# Communication.net
KiCad netlist of a schematic drawn in Altium Designer
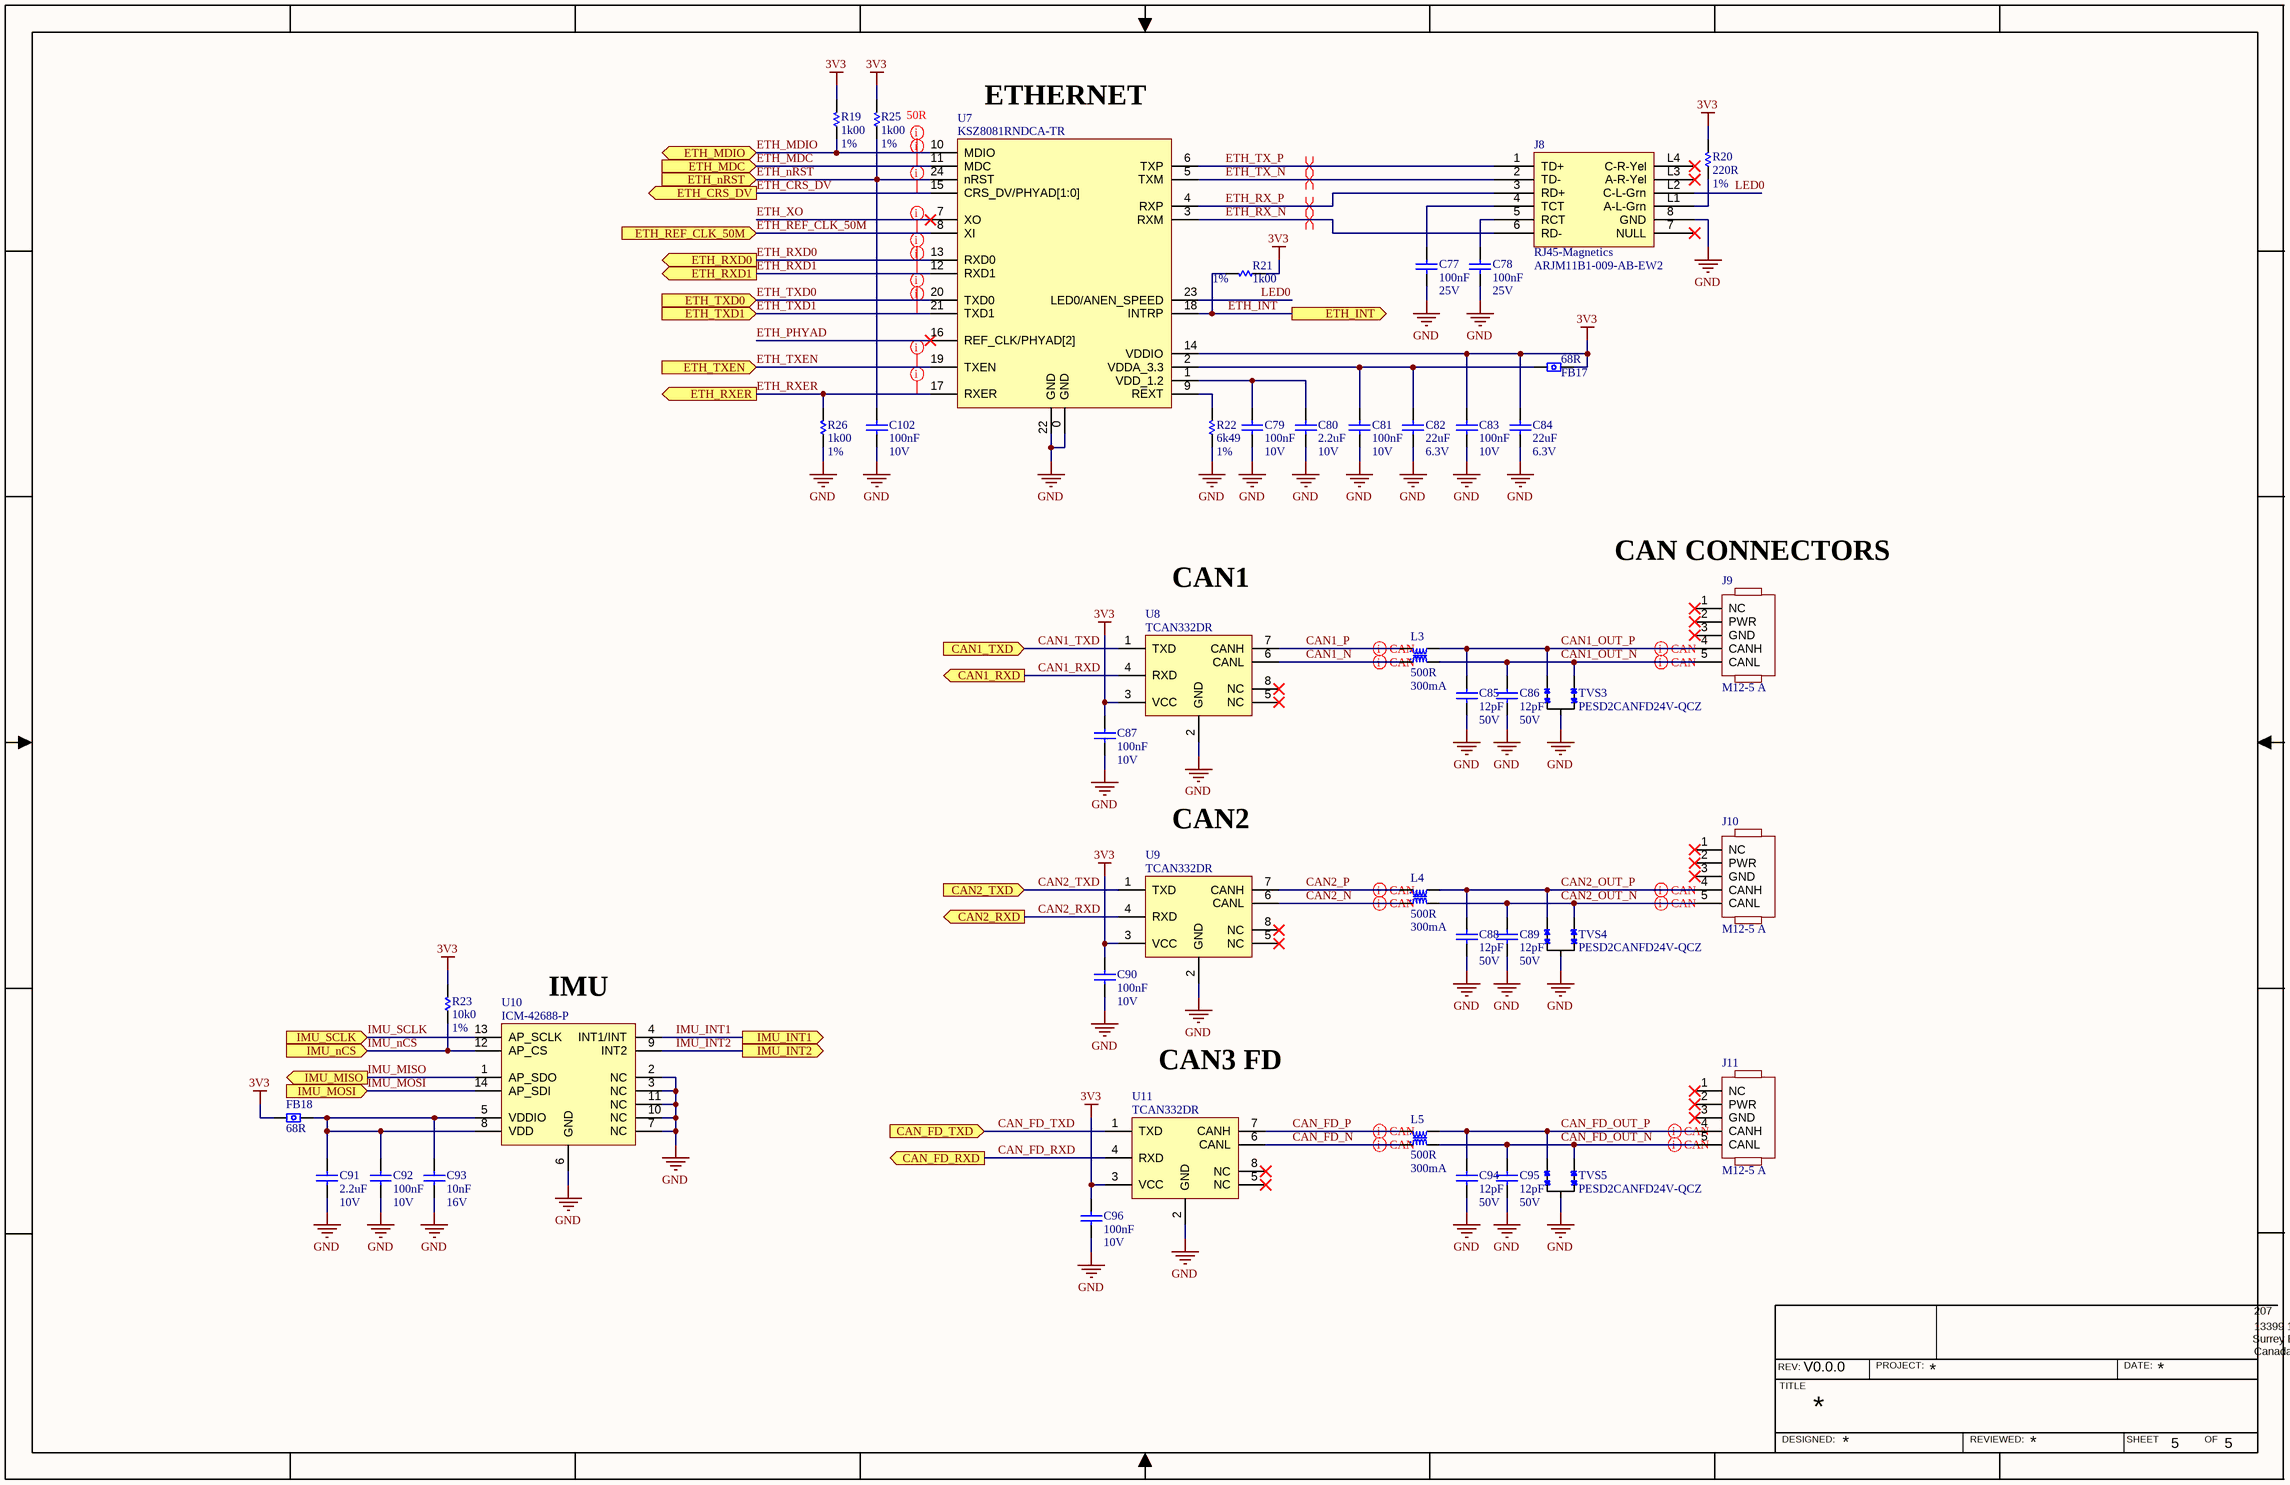
[diagram p0: Communication.SchDoc]

(export (version "E")
  (design (tool "Eeschema 10.0.6"))
  (components
    (comp (ref "C77")
      (value "100nF")
      (footprint "C0402")
      (description "Cap Ceramic 0.1uF 25V X5R 10% Pad SMD 0402 85°C T/R / Multi Layer Ceramic Capacitor (MLCC)")
      (fields
        (field (name "MANUFACTURER") "Samsung")
        (field (name "MANUFACTURER PART NUMBER") "CL05A104KA5NNNC")
        (field (name "VOLTAGE RATING") "25V")
      )
      (libsource (lib "MCU") (part "CAP CER 100nF 25V X5R 0402"))
    )
    (comp (ref "C78")
      (value "100nF")
      (footprint "C0402")
      (description "Cap Ceramic 0.1uF 25V X5R 10% Pad SMD 0402 85°C T/R / Multi Layer Ceramic Capacitor (MLCC)")
      (fields
        (field (name "MANUFACTURER") "Samsung")
        (field (name "MANUFACTURER PART NUMBER") "CL05A104KA5NNNC")
        (field (name "VOLTAGE RATING") "25V")
      )
      (libsource (lib "MCU") (part "CAP CER 100nF 25V X5R 0402"))
    )
    (comp (ref "C79")
      (value "100nF")
      (footprint "C0201")
      (description "CAP CER 0.1UF 10V X5R 0201")
      (fields (field (name "TOLERANCE") "20%") (field (name "VOLTAGE RATING") "10V"))
      (libsource (lib "MCU") (part "CAP CER 100nF 10V X5R 0201"))
    )
    (comp (ref "C80")
      (value "2.2uF")
      (footprint "C0402")
      (fields
        (field (name "MANUFACTURER") "Taiyo Yuden")
        (field (name "MANUFACTURER PART NUMBER") "LMK105BJ225MV-F")
        (field (name "TOLERANCE") "20%")
        (field (name "VOLTAGE RATING") "10V")
      )
      (libsource (lib "MCU") (part "CAP CER 2.2uF 10V X5R 0402"))
    )
    (comp (ref "C81")
      (value "100nF")
      (footprint "C0201")
      (description "CAP CER 0.1UF 10V X5R 0201")
      (fields (field (name "TOLERANCE") "20%") (field (name "VOLTAGE RATING") "10V"))
      (libsource (lib "MCU") (part "CAP CER 100nF 10V X5R 0201"))
    )
    (comp (ref "C82")
      (value "22uF")
      (footprint "C0805")
      (description "CAP CER 22UF 6.3V X5R 0805 / Cap Ceramic 22uF 6.3V X5R 20% Pad SMD 0805 85°C T/R")
      (fields
        (field (name "MANUFACTURER") "Samsung")
        (field (name "MANUFACTURER PART NUMBER") "CL21A226MQQNNNE")
        (field (name "VOLTAGE RATING (DC)") "6.3V")
      )
      (libsource (lib "MCU") (part "CAP CER 22uF 6.3V X5R 0805"))
    )
    (comp (ref "C83")
      (value "100nF")
      (footprint "C0201")
      (description "CAP CER 0.1UF 10V X5R 0201")
      (fields (field (name "TOLERANCE") "20%") (field (name "VOLTAGE RATING") "10V"))
      (libsource (lib "MCU") (part "CAP CER 100nF 10V X5R 0201"))
    )
    (comp (ref "C84")
      (value "22uF")
      (footprint "C0805")
      (description "CAP CER 22UF 6.3V X5R 0805 / Cap Ceramic 22uF 6.3V X5R 20% Pad SMD 0805 85°C T/R")
      (fields
        (field (name "MANUFACTURER") "Samsung")
        (field (name "MANUFACTURER PART NUMBER") "CL21A226MQQNNNE")
        (field (name "VOLTAGE RATING (DC)") "6.3V")
      )
      (libsource (lib "MCU") (part "CAP CER 22uF 6.3V X5R 0805"))
    )
    (comp (ref "C85")
      (value "12pF")
      (footprint "C0402")
      (description "Ceramic capacitor SMD-0402 12pF /50V C0G# J +-5%, Samsung, RoHS")
      (fields
        (field (name "MANUFACTURER") "Samsung")
        (field (name "MANUFACTURER PART NUMBER") "CL05C120JB5NNNC")
        (field (name "VOLTAGE") "50V")
      )
      (libsource (lib "MCU") (part "CAP CER 12pF 50V C0G 0402"))
    )
    (comp (ref "C86")
      (value "12pF")
      (footprint "C0402")
      (description "Ceramic capacitor SMD-0402 12pF /50V C0G# J +-5%, Samsung, RoHS")
      (fields
        (field (name "MANUFACTURER") "Samsung")
        (field (name "MANUFACTURER PART NUMBER") "CL05C120JB5NNNC")
        (field (name "VOLTAGE") "50V")
      )
      (libsource (lib "MCU") (part "CAP CER 12pF 50V C0G 0402"))
    )
    (comp (ref "C87")
      (value "100nF")
      (footprint "C0201")
      (description "CAP CER 0.1UF 10V X5R 0201")
      (fields (field (name "TOLERANCE") "20%") (field (name "VOLTAGE RATING") "10V"))
      (libsource (lib "MCU") (part "CAP CER 100nF 10V X5R 0201"))
    )
    (comp (ref "C88")
      (value "12pF")
      (footprint "C0402")
      (description "Ceramic capacitor SMD-0402 12pF /50V C0G# J +-5%, Samsung, RoHS")
      (fields
        (field (name "MANUFACTURER") "Samsung")
        (field (name "MANUFACTURER PART NUMBER") "CL05C120JB5NNNC")
        (field (name "VOLTAGE") "50V")
      )
      (libsource (lib "MCU") (part "CAP CER 12pF 50V C0G 0402"))
    )
    (comp (ref "C89")
      (value "12pF")
      (footprint "C0402")
      (description "Ceramic capacitor SMD-0402 12pF /50V C0G# J +-5%, Samsung, RoHS")
      (fields
        (field (name "MANUFACTURER") "Samsung")
        (field (name "MANUFACTURER PART NUMBER") "CL05C120JB5NNNC")
        (field (name "VOLTAGE") "50V")
      )
      (libsource (lib "MCU") (part "CAP CER 12pF 50V C0G 0402"))
    )
    (comp (ref "C90")
      (value "100nF")
      (footprint "C0201")
      (description "CAP CER 0.1UF 10V X5R 0201")
      (fields (field (name "TOLERANCE") "20%") (field (name "VOLTAGE RATING") "10V"))
      (libsource (lib "MCU") (part "CAP CER 100nF 10V X5R 0201"))
    )
    (comp (ref "C91")
      (value "2.2uF")
      (footprint "C0402")
      (fields
        (field (name "MANUFACTURER") "Taiyo Yuden")
        (field (name "MANUFACTURER PART NUMBER") "LMK105BJ225MV-F")
        (field (name "TOLERANCE") "20%")
        (field (name "VOLTAGE RATING") "10V")
      )
      (libsource (lib "MCU") (part "CAP CER 2.2uF 10V X5R 0402"))
    )
    (comp (ref "C92")
      (value "100nF")
      (footprint "C0201")
      (description "CAP CER 0.1UF 10V X5R 0201")
      (fields (field (name "TOLERANCE") "20%") (field (name "VOLTAGE RATING") "10V"))
      (libsource (lib "MCU") (part "CAP CER 100nF 10V X5R 0201"))
    )
    (comp (ref "C93")
      (value "10nF")
      (footprint "c0402")
      (description "0402 10 nF 16 V -20 / +80 % Tolerance Y5V SMT Multilayer Ceramic Capacitor")
      (fields
        (field (name "MANUFACTURER") "Yageo")
        (field (name "MANUFACTURER PART NUMBER") "CC0402ZRY5V7BB103")
        (field (name "VOLTAGE RATING") "16V")
      )
      (libsource (lib "MCU") (part "CAP CER 10nF 16V Y5V 0402"))
    )
    (comp (ref "C94")
      (value "12pF")
      (footprint "C0402")
      (description "Ceramic capacitor SMD-0402 12pF /50V C0G# J +-5%, Samsung, RoHS")
      (fields
        (field (name "MANUFACTURER") "Samsung")
        (field (name "MANUFACTURER PART NUMBER") "CL05C120JB5NNNC")
        (field (name "VOLTAGE") "50V")
      )
      (libsource (lib "MCU") (part "CAP CER 12pF 50V C0G 0402"))
    )
    (comp (ref "C95")
      (value "12pF")
      (footprint "C0402")
      (description "Ceramic capacitor SMD-0402 12pF /50V C0G# J +-5%, Samsung, RoHS")
      (fields
        (field (name "MANUFACTURER") "Samsung")
        (field (name "MANUFACTURER PART NUMBER") "CL05C120JB5NNNC")
        (field (name "VOLTAGE") "50V")
      )
      (libsource (lib "MCU") (part "CAP CER 12pF 50V C0G 0402"))
    )
    (comp (ref "C96")
      (value "100nF")
      (footprint "C0201")
      (description "CAP CER 0.1UF 10V X5R 0201")
      (fields (field (name "TOLERANCE") "20%") (field (name "VOLTAGE RATING") "10V"))
      (libsource (lib "MCU") (part "CAP CER 100nF 10V X5R 0201"))
    )
    (comp (ref "C102")
      (value "100nF")
      (footprint "C0201")
      (description "CAP CER 0.1UF 10V X5R 0201")
      (fields (field (name "TOLERANCE") "20%") (field (name "VOLTAGE RATING") "10V"))
      (libsource (lib "MCU") (part "CAP CER 100nF 10V X5R 0201"))
    )
    (comp (ref "FB17")
      (value "68R")
      (footprint "FB0402")
      (description "Ferrite Beads Multi-Layer 68Ohm 25% 100MHz 400mA 310mOhm DCR 0402 T/R")
      (fields
        (field (name "MANUFACTURER") "Taiyo Yuden")
        (field (name "MANUFACTURER PART NUMBER") "BK1005LL680-T")
      )
      (libsource (lib "MCU") (part "FB 68R 400mA 310mR 0402"))
    )
    (comp (ref "FB18")
      (value "68R")
      (footprint "FB0402")
      (description "Ferrite Beads Multi-Layer 68Ohm 25% 100MHz 400mA 310mOhm DCR 0402 T/R")
      (fields
        (field (name "MANUFACTURER") "Taiyo Yuden")
        (field (name "MANUFACTURER PART NUMBER") "BK1005LL680-T")
      )
      (libsource (lib "MCU") (part "FB 68R 400mA 310mR 0402"))
    )
    (comp (ref "J8")
      (value "RJ45-Magnetics")
      (footprint "RJ45_ARJM11B1_LED")
      (description "RJ45 Integrated T-Base 100 Magnetics")
      (fields (field (name "SUPPLIER PART NUMBER 1") "ARJM11B1-009-AB-EW2"))
      (libsource (lib "MCU") (part "ARJM11B1-009-AB-EW2"))
    )
    (comp (ref "J9")
      (value "M12-5 A")
      (footprint "M12-5A RA TH")
      (description "Connector, Circular, Plug, 5 Position, Right Angle, Panel Mount")
      (fields
        (field (name "MANUFACTURER") "TE Connectivity AMP")
        (field (name "MANUFACTURER PART NUMBER") "T4144015051-000")
      )
      (libsource (lib "MCU") (part "CON M12-5A T4144015051-000"))
    )
    (comp (ref "J10")
      (value "M12-5 A")
      (footprint "M12-5A RA TH")
      (description "Connector, Circular, Plug, 5 Position, Right Angle, Panel Mount")
      (fields
        (field (name "MANUFACTURER") "TE Connectivity AMP")
        (field (name "MANUFACTURER PART NUMBER") "T4144015051-000")
      )
      (libsource (lib "MCU") (part "CON M12-5A T4144015051-000"))
    )
    (comp (ref "J11")
      (value "M12-5 A")
      (footprint "M12-5A RA TH")
      (description "Connector, Circular, Plug, 5 Position, Right Angle, Panel Mount")
      (fields
        (field (name "MANUFACTURER") "TE Connectivity AMP")
        (field (name "MANUFACTURER PART NUMBER") "T4144015051-000")
      )
      (libsource (lib "MCU") (part "CON M12-5A T4144015051-000"))
    )
    (comp (ref "L3")
      (value "500R")
      (footprint "IND CHOKE 1.2x2")
      (description "Common Mode Chokes Dual 500Ohm 100MHz 300mA 500mOhm DCR SMD T/R")
      (fields
        (field (name "MANUFACTURER") "Bourns")
        (field (name "MANUFACTURER PART NUMBER") "SRF2012-501YA")
        (field (name "MAX CURRENT RATING") "300mA")
      )
      (libsource (lib "MCU") (part "IND CM 500R 300mA SRF2012-501YA"))
    )
    (comp (ref "L4")
      (value "500R")
      (footprint "IND CHOKE 1.2x2")
      (description "Common Mode Chokes Dual 500Ohm 100MHz 300mA 500mOhm DCR SMD T/R")
      (fields
        (field (name "MANUFACTURER") "Bourns")
        (field (name "MANUFACTURER PART NUMBER") "SRF2012-501YA")
        (field (name "MAX CURRENT RATING") "300mA")
      )
      (libsource (lib "MCU") (part "IND CM 500R 300mA SRF2012-501YA"))
    )
    (comp (ref "L5")
      (value "500R")
      (footprint "IND CHOKE 1.2x2")
      (description "Common Mode Chokes Dual 500Ohm 100MHz 300mA 500mOhm DCR SMD T/R")
      (fields
        (field (name "MANUFACTURER") "Bourns")
        (field (name "MANUFACTURER PART NUMBER") "SRF2012-501YA")
        (field (name "MAX CURRENT RATING") "300mA")
      )
      (libsource (lib "MCU") (part "IND CM 500R 300mA SRF2012-501YA"))
    )
    (comp (ref "R19")
      (value "1k00")
      (footprint "R0402")
      (description "1 kOhms ±1% 0.063W, 1/16W Chip Resistor 0402 (1005 Metric) Moisture Resistant Thick Film")
      (fields
        (field (name "MANUFACTURER") "Yageo")
        (field (name "MANUFACTURER PART NUMBER") "RC0402FR-071KL")
        (field (name "TOLERANCE") "1%")
      )
      (libsource (lib "MCU") (part "RES 1k00 63mW 0402"))
    )
    (comp (ref "R20")
      (value "220R")
      (footprint "R0402")
      (description "Res Thick Film 0402 220 Ohm 1% 0.063W ?100ppm/?C Molded SMD Paper T/R")
      (fields
        (field (name "MANUFACTURER") "Yageo")
        (field (name "MANUFACTURER PART NUMBER") "RC0402FR-07220RL")
        (field (name "TOLERANCE") "1%")
      )
      (libsource (lib "MCU") (part "RES 220R 1% 63mW 0402"))
    )
    (comp (ref "R21")
      (value "1k00")
      (footprint "R0402")
      (description "1 kOhms ±1% 0.063W, 1/16W Chip Resistor 0402 (1005 Metric) Moisture Resistant Thick Film")
      (fields
        (field (name "MANUFACTURER") "Yageo")
        (field (name "MANUFACTURER PART NUMBER") "RC0402FR-071KL")
        (field (name "TOLERANCE") "1%")
      )
      (libsource (lib "MCU") (part "RES 1k00 63mW 0402"))
    )
    (comp (ref "R22")
      (value "6k49")
      (footprint "r0402")
      (description "Res Thick Film 0402 6.49K Ohm 1% 1/10W ±100ppm/°C Molded SMD Punched Carrier T/R")
      (fields
        (field (name "MANUFACTURER") "Panasonic")
        (field (name "MANUFACTURER PART NUMBER") "ERJ-2RKF6491X")
        (field (name "TOLERANCE") "1%")
      )
      (libsource (lib "MCU") (part "RES 6k49 1% 63mW 0402"))
    )
    (comp (ref "R23")
      (value "10k0")
      (footprint "r0402")
      (description "Res General Purpose Thick Film 0402 10K Ohm 1% 1/16W ±100ppm/°C Molded SMD Paper T/R")
      (fields
        (field (name "MANUFACTURER") "Yageo")
        (field (name "MANUFACTURER PART NUMBER") "RC0402FR-0710KL")
        (field (name "TOLERANCE") "1%")
      )
      (libsource (lib "MCU") (part "RES 10k0 1% 63mW 0402"))
    )
    (comp (ref "R25")
      (value "1k00")
      (footprint "R0402")
      (description "1 kOhms ±1% 0.063W, 1/16W Chip Resistor 0402 (1005 Metric) Moisture Resistant Thick Film")
      (fields
        (field (name "MANUFACTURER") "Yageo")
        (field (name "MANUFACTURER PART NUMBER") "RC0402FR-071KL")
        (field (name "TOLERANCE") "1%")
      )
      (libsource (lib "MCU") (part "RES 1k00 63mW 0402"))
    )
    (comp (ref "R26")
      (value "1k00")
      (footprint "R0402")
      (description "1 kOhms ±1% 0.063W, 1/16W Chip Resistor 0402 (1005 Metric) Moisture Resistant Thick Film")
      (fields
        (field (name "MANUFACTURER") "Yageo")
        (field (name "MANUFACTURER PART NUMBER") "RC0402FR-071KL")
        (field (name "TOLERANCE") "1%")
      )
      (libsource (lib "MCU") (part "RES 1k00 63mW 0402"))
    )
    (comp (ref "TVS3")
      (value "PESD2CANFD24V-QCZ")
      (footprint "DFN1412D-3")
      (description "PESD2CANFD24V-QC - ESD protection for In-vehicle networks")
      (fields (field (name "MANUFACTURER") "Nexperia"))
      (libsource (lib "MCU") (part "DIODE TVS 24V 2chanPESD2CANFD24V-QCZ"))
    )
    (comp (ref "TVS4")
      (value "PESD2CANFD24V-QCZ")
      (footprint "DFN1412D-3")
      (description "PESD2CANFD24V-QC - ESD protection for In-vehicle networks")
      (fields (field (name "MANUFACTURER") "Nexperia"))
      (libsource (lib "MCU") (part "DIODE TVS 24V 2chanPESD2CANFD24V-QCZ"))
    )
    (comp (ref "TVS5")
      (value "PESD2CANFD24V-QCZ")
      (footprint "DFN1412D-3")
      (description "PESD2CANFD24V-QC - ESD protection for In-vehicle networks")
      (fields (field (name "MANUFACTURER") "Nexperia"))
      (libsource (lib "MCU") (part "DIODE TVS 24V 2chanPESD2CANFD24V-QCZ"))
    )
    (comp (ref "U7")
      (value "KSZ8081RNDCA-TR")
      (footprint "QFN50P400X400X90_HS-25N")
      (description "Ethernet PHY, 100Mbps, -40 to 85°C, VQFN-24, RoHS")
      (fields
        (field (name "MANUFACTURER") "Microchip")
        (field (name "MANUFACTURER PART NUMBER") "KSZ8081RNDCATR")
      )
      (libsource (lib "MCU") (part "IC ETH PHY 10-100M RMII KSZ8081RNDCATR"))
    )
    (comp (ref "U8")
      (value "TCAN332DR")
      (footprint "SO8 6.2x5mm TI D0008A")
      (description "IC TXRX CAN 3.3V 8SOIC")
      (fields (field (name "MANUFACTURER") "Texas Instruments"))
      (libsource (lib "MCU") (part "IC CAN TRX TCAN332DR"))
    )
    (comp (ref "U9")
      (value "TCAN332DR")
      (footprint "SO8 6.2x5mm TI D0008A")
      (description "IC TXRX CAN 3.3V 8SOIC")
      (fields (field (name "MANUFACTURER") "Texas Instruments"))
      (libsource (lib "MCU") (part "IC CAN TRX TCAN332DR"))
    )
    (comp (ref "U10")
      (value "ICM-42688-P")
      (footprint "PQFN50P300X250X97-14 ICM-42688-P")
      (description "Accelerometer and Gyroscope 6-Axis MEMS Motion Tracking Device Digital-OUT 14-Pin LGA T/R")
      (fields (field (name "MANUFACTURER") "TDK InvenSense"))
      (libsource (lib "MCU") (part "IC IMU 6DOF ICM-42688-P"))
    )
    (comp (ref "U11")
      (value "TCAN332DR")
      (footprint "SO8 6.2x5mm TI D0008A")
      (description "IC TXRX CAN 3.3V 8SOIC")
      (fields (field (name "MANUFACTURER") "Texas Instruments"))
      (libsource (lib "MCU") (part "IC CAN TRX TCAN332DR"))
    )
  )
  (nets
    (net (code "1") (name "/CAN1_N") (class "Default")
      (node (ref "L3") (pin "4") (pinfunction "4_4") (pintype "passive"))
      (node (ref "U8") (pin "6") (pinfunction "CANL_6") (pintype "passive"))
    )
    (net (code "2") (name "/CAN1_OUT_N") (class "Default")
      (node (ref "C86") (pin "2") (pinfunction "2_2") (pintype "passive"))
      (node (ref "J9") (pin "5") (pinfunction "CANL_5") (pintype "passive"))
      (node (ref "L3") (pin "3") (pinfunction "3_3") (pintype "passive"))
      (node (ref "TVS3") (pin "2") (pinfunction "2_2") (pintype "passive"))
    )
    (net (code "3") (name "/CAN1_OUT_P") (class "Default")
      (node (ref "C85") (pin "2") (pinfunction "2_2") (pintype "passive"))
      (node (ref "J9") (pin "4") (pinfunction "CANH_4") (pintype "passive"))
      (node (ref "L3") (pin "2") (pinfunction "2_2") (pintype "passive"))
      (node (ref "TVS3") (pin "1") (pinfunction "1_1") (pintype "passive"))
    )
    (net (code "4") (name "/CAN1_P") (class "Default")
      (node (ref "L3") (pin "1") (pinfunction "1_1") (pintype "passive"))
      (node (ref "U8") (pin "7") (pinfunction "CANH_7") (pintype "passive"))
    )
    (net (code "5") (name "/CAN1_RXD") (class "Default")
      (node (ref "U8") (pin "4") (pinfunction "RXD_4") (pintype "passive"))
    )
    (net (code "6") (name "/CAN1_TXD") (class "Default")
      (node (ref "U8") (pin "1") (pinfunction "TXD_1") (pintype "passive"))
    )
    (net (code "7") (name "/CAN2_N") (class "Default")
      (node (ref "L4") (pin "4") (pinfunction "4_4") (pintype "passive"))
      (node (ref "U9") (pin "6") (pinfunction "CANL_6") (pintype "passive"))
    )
    (net (code "8") (name "/CAN2_OUT_N") (class "Default")
      (node (ref "C89") (pin "2") (pinfunction "2_2") (pintype "passive"))
      (node (ref "J10") (pin "5") (pinfunction "CANL_5") (pintype "passive"))
      (node (ref "L4") (pin "3") (pinfunction "3_3") (pintype "passive"))
      (node (ref "TVS4") (pin "2") (pinfunction "2_2") (pintype "passive"))
    )
    (net (code "9") (name "/CAN2_OUT_P") (class "Default")
      (node (ref "C88") (pin "2") (pinfunction "2_2") (pintype "passive"))
      (node (ref "J10") (pin "4") (pinfunction "CANH_4") (pintype "passive"))
      (node (ref "L4") (pin "2") (pinfunction "2_2") (pintype "passive"))
      (node (ref "TVS4") (pin "1") (pinfunction "1_1") (pintype "passive"))
    )
    (net (code "10") (name "/CAN2_P") (class "Default")
      (node (ref "L4") (pin "1") (pinfunction "1_1") (pintype "passive"))
      (node (ref "U9") (pin "7") (pinfunction "CANH_7") (pintype "passive"))
    )
    (net (code "11") (name "/CAN2_RXD") (class "Default")
      (node (ref "U9") (pin "4") (pinfunction "RXD_4") (pintype "passive"))
    )
    (net (code "12") (name "/CAN2_TXD") (class "Default")
      (node (ref "U9") (pin "1") (pinfunction "TXD_1") (pintype "passive"))
    )
    (net (code "13") (name "/CAN_FD_N") (class "Default")
      (node (ref "L5") (pin "4") (pinfunction "4_4") (pintype "passive"))
      (node (ref "U11") (pin "6") (pinfunction "CANL_6") (pintype "passive"))
    )
    (net (code "14") (name "/CAN_FD_OUT_N") (class "Default")
      (node (ref "C95") (pin "2") (pinfunction "2_2") (pintype "passive"))
      (node (ref "J11") (pin "5") (pinfunction "CANL_5") (pintype "passive"))
      (node (ref "L5") (pin "3") (pinfunction "3_3") (pintype "passive"))
      (node (ref "TVS5") (pin "2") (pinfunction "2_2") (pintype "passive"))
    )
    (net (code "15") (name "/CAN_FD_OUT_P") (class "Default")
      (node (ref "C94") (pin "2") (pinfunction "2_2") (pintype "passive"))
      (node (ref "J11") (pin "4") (pinfunction "CANH_4") (pintype "passive"))
      (node (ref "L5") (pin "2") (pinfunction "2_2") (pintype "passive"))
      (node (ref "TVS5") (pin "1") (pinfunction "1_1") (pintype "passive"))
    )
    (net (code "16") (name "/CAN_FD_P") (class "Default")
      (node (ref "L5") (pin "1") (pinfunction "1_1") (pintype "passive"))
      (node (ref "U11") (pin "7") (pinfunction "CANH_7") (pintype "passive"))
    )
    (net (code "17") (name "/CAN_FD_RXD") (class "Default")
      (node (ref "U11") (pin "4") (pinfunction "RXD_4") (pintype "passive"))
    )
    (net (code "18") (name "/CAN_FD_TXD") (class "Default")
      (node (ref "U11") (pin "1") (pinfunction "TXD_1") (pintype "passive"))
    )
    (net (code "19") (name "/ETH_CRS_DV") (class "Default")
      (node (ref "U7") (pin "15") (pinfunction "CRS_DV/PHYAD[1:0]_15") (pintype "passive"))
    )
    (net (code "20") (name "/ETH_INT") (class "Default")
      (node (ref "R21") (pin "2") (pinfunction "2_2") (pintype "passive"))
      (node (ref "U7") (pin "18") (pinfunction "INTRP_18") (pintype "passive"))
    )
    (net (code "21") (name "/ETH_MDC") (class "Default")
      (node (ref "U7") (pin "11") (pinfunction "MDC_11") (pintype "passive"))
    )
    (net (code "22") (name "/ETH_MDIO") (class "Default")
      (node (ref "R19") (pin "1") (pinfunction "1_1") (pintype "passive"))
      (node (ref "U7") (pin "10") (pinfunction "MDIO_10") (pintype "passive"))
    )
    (net (code "23") (name "/ETH_PHYAD") (class "Default")
      (node (ref "U7") (pin "16") (pinfunction "REF_CLK/PHYAD[2]_16") (pintype "passive+no_connect"))
    )
    (net (code "24") (name "/ETH_REF_CLK_50M") (class "Default")
      (node (ref "U7") (pin "8") (pinfunction "XI_8") (pintype "passive"))
    )
    (net (code "25") (name "/ETH_RXD0") (class "Default")
      (node (ref "U7") (pin "13") (pinfunction "RXD0_13") (pintype "passive"))
    )
    (net (code "26") (name "/ETH_RXD1") (class "Default")
      (node (ref "U7") (pin "12") (pinfunction "RXD1_12") (pintype "passive"))
    )
    (net (code "27") (name "/ETH_RXER") (class "Default")
      (node (ref "R26") (pin "2") (pinfunction "2_2") (pintype "passive"))
      (node (ref "U7") (pin "17") (pinfunction "RXER_17") (pintype "passive"))
    )
    (net (code "28") (name "/ETH_RX_N") (class "Default")
      (node (ref "J8") (pin "6") (pinfunction "RD-_6") (pintype "passive"))
      (node (ref "U7") (pin "3") (pinfunction "RXM_3") (pintype "passive"))
    )
    (net (code "29") (name "/ETH_RX_P") (class "Default")
      (node (ref "J8") (pin "3") (pinfunction "RD+_3") (pintype "passive"))
      (node (ref "U7") (pin "4") (pinfunction "RXP_4") (pintype "passive"))
    )
    (net (code "30") (name "/ETH_TXD0") (class "Default")
      (node (ref "U7") (pin "20") (pinfunction "TXD0_20") (pintype "passive"))
    )
    (net (code "31") (name "/ETH_TXD1") (class "Default")
      (node (ref "U7") (pin "21") (pinfunction "TXD1_21") (pintype "passive"))
    )
    (net (code "32") (name "/ETH_TXEN") (class "Default")
      (node (ref "U7") (pin "19") (pinfunction "TXEN_19") (pintype "passive"))
    )
    (net (code "33") (name "/ETH_TX_N") (class "Default")
      (node (ref "J8") (pin "2") (pinfunction "TD-_2") (pintype "passive"))
      (node (ref "U7") (pin "5") (pinfunction "TXM_5") (pintype "passive"))
    )
    (net (code "34") (name "/ETH_TX_P") (class "Default")
      (node (ref "J8") (pin "1") (pinfunction "TD+_1") (pintype "passive"))
      (node (ref "U7") (pin "6") (pinfunction "TXP_6") (pintype "passive"))
    )
    (net (code "35") (name "/ETH_XO") (class "Default")
      (node (ref "U7") (pin "7") (pinfunction "XO_7") (pintype "passive+no_connect"))
    )
    (net (code "36") (name "/ETH_nRST") (class "Default")
      (node (ref "C102") (pin "2") (pinfunction "2_2") (pintype "passive"))
      (node (ref "R25") (pin "1") (pinfunction "1_1") (pintype "passive"))
      (node (ref "U7") (pin "24") (pinfunction "nRST_24") (pintype "passive"))
    )
    (net (code "37") (name "/IMU_INT1") (class "Default")
      (node (ref "U10") (pin "4") (pinfunction "INT1/INT_4") (pintype "passive"))
    )
    (net (code "38") (name "/IMU_INT2") (class "Default")
      (node (ref "U10") (pin "9") (pinfunction "INT2_9") (pintype "passive"))
    )
    (net (code "39") (name "/IMU_MISO") (class "Default")
      (node (ref "U10") (pin "1") (pinfunction "AP_SDO_1") (pintype "passive"))
    )
    (net (code "40") (name "/IMU_MOSI") (class "Default")
      (node (ref "U10") (pin "14") (pinfunction "AP_SDI_14") (pintype "passive"))
    )
    (net (code "41") (name "/IMU_SCLK") (class "Default")
      (node (ref "U10") (pin "13") (pinfunction "AP_SCLK_13") (pintype "passive"))
    )
    (net (code "42") (name "/IMU_nCS") (class "Default")
      (node (ref "R23") (pin "1") (pinfunction "1_1") (pintype "passive"))
      (node (ref "U10") (pin "12") (pinfunction "AP_CS_12") (pintype "passive"))
    )
    (net (code "43") (name "/LED0") (class "Default")
      (node (ref "J8") (pin "L2") (pinfunction "C-L-Grn_L2") (pintype "passive"))
      (node (ref "U7") (pin "23") (pinfunction "LED0/ANEN_SPEED_23") (pintype "passive"))
    )
    (net (code "44") (name "3V3") (class "Default")
      (node (ref "C83") (pin "2") (pinfunction "2_2") (pintype "passive"))
      (node (ref "C84") (pin "2") (pinfunction "2_2") (pintype "passive"))
      (node (ref "C87") (pin "2") (pinfunction "2_2") (pintype "passive"))
      (node (ref "C90") (pin "2") (pinfunction "2_2") (pintype "passive"))
      (node (ref "C96") (pin "2") (pinfunction "2_2") (pintype "passive"))
      (node (ref "FB17") (pin "1") (pintype "passive"))
      (node (ref "FB18") (pin "1") (pintype "passive"))
      (node (ref "R19") (pin "2") (pinfunction "2_2") (pintype "passive"))
      (node (ref "R20") (pin "2") (pinfunction "2_2") (pintype "passive"))
      (node (ref "R21") (pin "1") (pinfunction "1_1") (pintype "passive"))
      (node (ref "R23") (pin "2") (pinfunction "2_2") (pintype "passive"))
      (node (ref "R25") (pin "2") (pinfunction "2_2") (pintype "passive"))
      (node (ref "U11") (pin "3") (pinfunction "VCC_3") (pintype "passive"))
      (node (ref "U7") (pin "14") (pinfunction "VDDIO_14") (pintype "passive"))
      (node (ref "U8") (pin "3") (pinfunction "VCC_3") (pintype "passive"))
      (node (ref "U9") (pin "3") (pinfunction "VCC_3") (pintype "passive"))
    )
    (net (code "45") (name "GND") (class "Default")
      (node (ref "C102") (pin "1") (pinfunction "1_1") (pintype "passive"))
      (node (ref "C77") (pin "1") (pinfunction "1_1") (pintype "passive"))
      (node (ref "C78") (pin "1") (pinfunction "1_1") (pintype "passive"))
      (node (ref "C79") (pin "1") (pinfunction "1_1") (pintype "passive"))
      (node (ref "C80") (pin "1") (pinfunction "1_1") (pintype "passive"))
      (node (ref "C81") (pin "1") (pinfunction "1_1") (pintype "passive"))
      (node (ref "C82") (pin "1") (pinfunction "1_1") (pintype "passive"))
      (node (ref "C83") (pin "1") (pinfunction "1_1") (pintype "passive"))
      (node (ref "C84") (pin "1") (pinfunction "1_1") (pintype "passive"))
      (node (ref "C85") (pin "1") (pinfunction "1_1") (pintype "passive"))
      (node (ref "C86") (pin "1") (pinfunction "1_1") (pintype "passive"))
      (node (ref "C87") (pin "1") (pinfunction "1_1") (pintype "passive"))
      (node (ref "C88") (pin "1") (pinfunction "1_1") (pintype "passive"))
      (node (ref "C89") (pin "1") (pinfunction "1_1") (pintype "passive"))
      (node (ref "C90") (pin "1") (pinfunction "1_1") (pintype "passive"))
      (node (ref "C91") (pin "1") (pinfunction "1_1") (pintype "passive"))
      (node (ref "C92") (pin "1") (pinfunction "1_1") (pintype "passive"))
      (node (ref "C93") (pin "1") (pinfunction "1_1") (pintype "passive"))
      (node (ref "C94") (pin "1") (pinfunction "1_1") (pintype "passive"))
      (node (ref "C95") (pin "1") (pinfunction "1_1") (pintype "passive"))
      (node (ref "C96") (pin "1") (pinfunction "1_1") (pintype "passive"))
      (node (ref "J8") (pin "8") (pinfunction "GND_8") (pintype "passive"))
      (node (ref "R22") (pin "1") (pinfunction "1_1") (pintype "passive"))
      (node (ref "R26") (pin "1") (pinfunction "1_1") (pintype "passive"))
      (node (ref "TVS3") (pin "3") (pinfunction "3_3") (pintype "passive"))
      (node (ref "TVS4") (pin "3") (pinfunction "3_3") (pintype "passive"))
      (node (ref "TVS5") (pin "3") (pinfunction "3_3") (pintype "passive"))
      (node (ref "U10") (pin "10") (pinfunction "NC_10") (pintype "passive"))
      (node (ref "U10") (pin "11") (pinfunction "NC_11") (pintype "passive"))
      (node (ref "U10") (pin "2") (pinfunction "NC_2") (pintype "passive"))
      (node (ref "U10") (pin "3") (pinfunction "NC_3") (pintype "passive"))
      (node (ref "U10") (pin "6") (pinfunction "GND_6") (pintype "passive"))
      (node (ref "U10") (pin "7") (pinfunction "NC_7") (pintype "passive"))
      (node (ref "U11") (pin "2") (pinfunction "GND_2") (pintype "passive"))
      (node (ref "U7") (pin "0") (pinfunction "GND_0") (pintype "passive"))
      (node (ref "U7") (pin "22") (pinfunction "GND_22") (pintype "passive"))
      (node (ref "U8") (pin "2") (pinfunction "GND_2") (pintype "passive"))
      (node (ref "U9") (pin "2") (pinfunction "GND_2") (pintype "passive"))
    )
    (net (code "46") (name "Net-(J8-A-L-Grn)") (class "Default")
      (node (ref "J8") (pin "L1") (pinfunction "A-L-Grn_L1") (pintype "passive"))
      (node (ref "R20") (pin "1") (pinfunction "1_1") (pintype "passive"))
    )
    (net (code "47") (name "Net-(J8-RCT)") (class "Default")
      (node (ref "C78") (pin "2") (pinfunction "2_2") (pintype "passive"))
      (node (ref "J8") (pin "5") (pinfunction "RCT_5") (pintype "passive"))
    )
    (net (code "48") (name "Net-(J8-TCT)") (class "Default")
      (node (ref "C77") (pin "2") (pinfunction "2_2") (pintype "passive"))
      (node (ref "J8") (pin "4") (pinfunction "TCT_4") (pintype "passive"))
    )
    (net (code "49") (name "Net-(U7-REXT)") (class "Default")
      (node (ref "R22") (pin "2") (pinfunction "2_2") (pintype "passive"))
      (node (ref "U7") (pin "9") (pinfunction "REXT_9") (pintype "passive"))
    )
    (net (code "50") (name "Net-(U7-VDDA_3.3)") (class "Default")
      (node (ref "C81") (pin "2") (pinfunction "2_2") (pintype "passive"))
      (node (ref "C82") (pin "2") (pinfunction "2_2") (pintype "passive"))
      (node (ref "FB17") (pin "2") (pintype "passive"))
      (node (ref "U7") (pin "2") (pinfunction "VDDA_3.3_2") (pintype "passive"))
    )
    (net (code "51") (name "Net-(U7-VDD_1.2)") (class "Default")
      (node (ref "C79") (pin "2") (pinfunction "2_2") (pintype "passive"))
      (node (ref "C80") (pin "2") (pinfunction "2_2") (pintype "passive"))
      (node (ref "U7") (pin "1") (pinfunction "VDD_1.2_1") (pintype "passive"))
    )
    (net (code "52") (name "Net-(U10-VDD)") (class "Default")
      (node (ref "C91") (pin "2") (pinfunction "2_2") (pintype "passive"))
      (node (ref "C92") (pin "2") (pinfunction "2_2") (pintype "passive"))
      (node (ref "C93") (pin "2") (pinfunction "2_2") (pintype "passive"))
      (node (ref "FB18") (pin "2") (pintype "passive"))
      (node (ref "U10") (pin "5") (pinfunction "VDDIO_5") (pintype "passive"))
      (node (ref "U10") (pin "8") (pinfunction "VDD_8") (pintype "passive"))
    )
    (net (code "53") (name "unconnected-(J8-A-R-Yel-PadL3)") (class "Default")
      (node (ref "J8") (pin "L3") (pinfunction "A-R-Yel_L3") (pintype "passive+no_connect"))
    )
    (net (code "54") (name "unconnected-(J8-C-R-Yel-PadL4)") (class "Default")
      (node (ref "J8") (pin "L4") (pinfunction "C-R-Yel_L4") (pintype "passive+no_connect"))
    )
    (net (code "55") (name "unconnected-(J8-NULL-Pad7)") (class "Default")
      (node (ref "J8") (pin "7") (pinfunction "NULL_7") (pintype "passive+no_connect"))
    )
    (net (code "56") (name "unconnected-(J9-GND-Pad3)") (class "Default")
      (node (ref "J9") (pin "3") (pinfunction "GND_3") (pintype "passive+no_connect"))
    )
    (net (code "57") (name "unconnected-(J9-NC-Pad1)") (class "Default")
      (node (ref "J9") (pin "1") (pinfunction "NC_1") (pintype "passive+no_connect"))
    )
    (net (code "58") (name "unconnected-(J9-PWR-Pad2)") (class "Default")
      (node (ref "J9") (pin "2") (pinfunction "PWR_2") (pintype "passive+no_connect"))
    )
    (net (code "59") (name "unconnected-(J10-GND-Pad3)") (class "Default")
      (node (ref "J10") (pin "3") (pinfunction "GND_3") (pintype "passive+no_connect"))
    )
    (net (code "60") (name "unconnected-(J10-NC-Pad1)") (class "Default")
      (node (ref "J10") (pin "1") (pinfunction "NC_1") (pintype "passive+no_connect"))
    )
    (net (code "61") (name "unconnected-(J10-PWR-Pad2)") (class "Default")
      (node (ref "J10") (pin "2") (pinfunction "PWR_2") (pintype "passive+no_connect"))
    )
    (net (code "62") (name "unconnected-(J11-GND-Pad3)") (class "Default")
      (node (ref "J11") (pin "3") (pinfunction "GND_3") (pintype "passive+no_connect"))
    )
    (net (code "63") (name "unconnected-(J11-NC-Pad1)") (class "Default")
      (node (ref "J11") (pin "1") (pinfunction "NC_1") (pintype "passive+no_connect"))
    )
    (net (code "64") (name "unconnected-(J11-PWR-Pad2)") (class "Default")
      (node (ref "J11") (pin "2") (pinfunction "PWR_2") (pintype "passive+no_connect"))
    )
    (net (code "65") (name "unconnected-(U8-NC-Pad5)") (class "Default")
      (node (ref "U8") (pin "5") (pinfunction "NC_5") (pintype "passive+no_connect"))
    )
    (net (code "66") (name "unconnected-(U8-NC-Pad8)") (class "Default")
      (node (ref "U8") (pin "8") (pinfunction "NC_8") (pintype "passive+no_connect"))
    )
    (net (code "67") (name "unconnected-(U9-NC-Pad5)") (class "Default")
      (node (ref "U9") (pin "5") (pinfunction "NC_5") (pintype "passive+no_connect"))
    )
    (net (code "68") (name "unconnected-(U9-NC-Pad8)") (class "Default")
      (node (ref "U9") (pin "8") (pinfunction "NC_8") (pintype "passive+no_connect"))
    )
    (net (code "69") (name "unconnected-(U11-NC-Pad5)") (class "Default")
      (node (ref "U11") (pin "5") (pinfunction "NC_5") (pintype "passive+no_connect"))
    )
    (net (code "70") (name "unconnected-(U11-NC-Pad8)") (class "Default")
      (node (ref "U11") (pin "8") (pinfunction "NC_8") (pintype "passive+no_connect"))
    )
  )
)
